# main_ftdi.net
KiCad netlist of a schematic drawn in Altium Designer
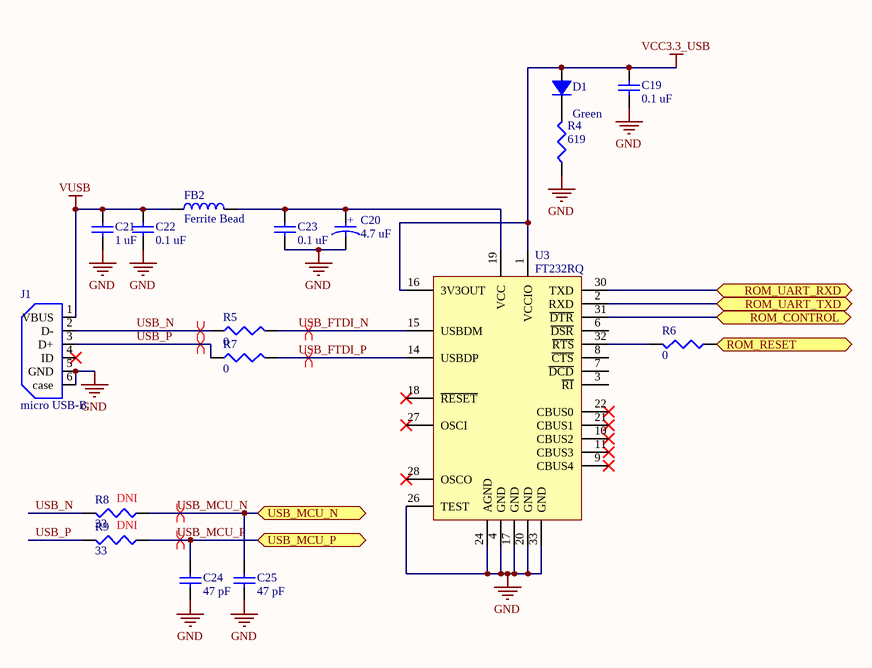
[diagram p0: main_ftdi.SchDoc]

(export (version "E")
  (design (tool "Eeschema 10.0.6"))
  (components
    (comp (ref "C19")
      (value "0.1 uF")
      (footprint "0402")
      (description "Ceramic capacitor, 0.1u, 0402 package")
      (fields (field (name "TOLERANCE") "10%") (field (name "Comment") "Ceramic capacitor"))
      (libsource (lib "rlc") (part "C_0.1u_0402_ceramic"))
    )
    (comp (ref "C20")
      (value "4.7 uF")
      (footprint "0603 - Polar Marking")
      (description "Tantalum capacitor, 4.7 uF, 0603 package")
      (fields (field (name "TOLERANCE") "20%") (field (name "Comment") "Tantalum capacitor"))
      (libsource (lib "rlc") (part "C_4.7u_0603_tantalum"))
    )
    (comp (ref "C21")
      (value "1 uF")
      (footprint "0402")
      (description "Ceramic capacitor, 1 uF, 0402 package")
      (fields (field (name "TOLERANCE") "10%") (field (name "Comment") "Ceramic capacitor"))
      (libsource (lib "rlc") (part "C_1u_0402_ceramic"))
    )
    (comp (ref "C22")
      (value "0.1 uF")
      (footprint "0402")
      (description "Ceramic capacitor, 0.1u, 0402 package")
      (fields (field (name "TOLERANCE") "10%") (field (name "Comment") "Ceramic capacitor"))
      (libsource (lib "rlc") (part "C_0.1u_0402_ceramic"))
    )
    (comp (ref "C23")
      (value "0.1 uF")
      (footprint "0402")
      (description "Ceramic capacitor, 0.1u, 0402 package")
      (fields (field (name "TOLERANCE") "10%") (field (name "Comment") "Ceramic capacitor"))
      (libsource (lib "rlc") (part "C_0.1u_0402_ceramic"))
    )
    (comp (ref "C24")
      (value "47 pF")
      (footprint "0402")
      (description "Ceramic capacitor, 47 pF, 0402 package")
      (fields (field (name "TOLERANCE") "5%") (field (name "Comment") "Ceramic capacitor"))
      (libsource (lib "rlc") (part "C_47p_0402_ceramic"))
    )
    (comp (ref "C25")
      (value "47 pF")
      (footprint "0402")
      (description "Ceramic capacitor, 47 pF, 0402 package")
      (fields (field (name "TOLERANCE") "5%") (field (name "Comment") "Ceramic capacitor"))
      (libsource (lib "rlc") (part "C_47p_0402_ceramic"))
    )
    (comp (ref "D1")
      (value "LED, Green")
      (footprint "0402 - DIODE")
      (description "LED, Green,  0402")
      (fields (field (name "COLOR") "Green"))
      (libsource (lib "rlc") (part "D_LED_GREEN_0402"))
    )
    (comp (ref "FB2")
      (value "Ferrite Bead")
      (footprint "0402")
      (description "Ferrite Bead, 150 mA, 0402 package")
      (libsource (lib "rlc") (part "FB_150mA_0402"))
    )
    (comp (ref "J1")
      (value "micro USB-B")
      (footprint "Micro USB-B")
      (description "CONN USB MICRO B RECPT SMT R/A")
      (libsource (lib "connectors") (part "Micro USB"))
    )
    (comp (ref "R4")
      (value "619")
      (footprint "0402")
      (description "Chip resistor, 619, 0402 package")
      (fields (field (name "TOLERANCE") "1%") (field (name "POWER") "1/16 W"))
      (libsource (lib "rlc") (part "R_619_0402"))
    )
    (comp (ref "R5")
      (value "0")
      (footprint "0402")
      (description "Chip resistor, 0, 0402 package")
      (fields (field (name "Comment") "Chip resistor"))
      (libsource (lib "rlc") (part "R_0_0402"))
    )
    (comp (ref "R6")
      (value "0")
      (footprint "0402")
      (description "Chip resistor, 0, 0402 package")
      (fields (field (name "Comment") "Chip resistor"))
      (libsource (lib "rlc") (part "R_0_0402"))
    )
    (comp (ref "R7")
      (value "0")
      (footprint "0402")
      (description "Chip resistor, 0, 0402 package")
      (fields (field (name "Comment") "Chip resistor"))
      (libsource (lib "rlc") (part "R_0_0402"))
    )
    (comp (ref "R8")
      (value "33")
      (footprint "0402")
      (description "Chip resistor, 33, 0402 package")
      (fields (field (name "TOLERANCE") "1%") (field (name "POWER") "1/16 W"))
      (libsource (lib "rlc") (part "R_33_0402"))
    )
    (comp (ref "R9")
      (value "33")
      (footprint "0402")
      (description "Chip resistor, 33, 0402 package")
      (fields (field (name "TOLERANCE") "1%") (field (name "POWER") "1/16 W"))
      (libsource (lib "rlc") (part "R_33_0402"))
    )
    (comp (ref "U3")
      (value "FT232RQ")
      (footprint "QFN-32")
      (description "FT232R USB UART")
      (libsource (lib "sdl") (part "FT232RQ"))
    )
  )
  (nets
    (net (code "1") (name "/ROM_CONTROL") (class "Default")
      (node (ref "U3") (pin "31") (pinfunction "~{DTR}_31") (pintype "passive"))
    )
    (net (code "2") (name "/ROM_RESET") (class "Default") (node (ref "R6") (pin "2") (pintype "passive")))
    (net (code "3") (name "/ROM_UART_RXD") (class "Default")
      (node (ref "U3") (pin "30") (pinfunction "TXD_30") (pintype "passive"))
    )
    (net (code "4") (name "/ROM_UART_TXD") (class "Default")
      (node (ref "U3") (pin "2") (pinfunction "RXD_2") (pintype "passive"))
    )
    (net (code "5") (name "/USB_FTDI_N") (class "Default")
      (node (ref "R5") (pin "1") (pintype "passive"))
      (node (ref "U3") (pin "15") (pinfunction "USBDM_15") (pintype "passive"))
    )
    (net (code "6") (name "/USB_FTDI_P") (class "Default")
      (node (ref "R7") (pin "1") (pintype "passive"))
      (node (ref "U3") (pin "14") (pinfunction "USBDP_14") (pintype "passive"))
    )
    (net (code "7") (name "/USB_MCU_N") (class "Default")
      (node (ref "C25") (pin "1") (pintype "passive"))
      (node (ref "R8") (pin "2") (pintype "passive"))
    )
    (net (code "8") (name "/USB_MCU_P") (class "Default")
      (node (ref "C24") (pin "1") (pintype "passive"))
      (node (ref "R9") (pin "2") (pintype "passive"))
    )
    (net (code "9") (name "/USB_N") (class "Default")
      (node (ref "J1") (pin "2") (pinfunction "D-_2") (pintype "power_in"))
      (node (ref "R5") (pin "2") (pintype "passive"))
      (node (ref "R8") (pin "1") (pintype "passive"))
    )
    (net (code "10") (name "/USB_P") (class "Default")
      (node (ref "J1") (pin "3") (pinfunction "D+_3") (pintype "power_in"))
      (node (ref "R7") (pin "2") (pintype "passive"))
      (node (ref "R9") (pin "1") (pintype "passive"))
    )
    (net (code "11") (name "GND") (class "Default")
      (node (ref "C19") (pin "2") (pintype "passive"))
      (node (ref "C20") (pin "2") (pintype "passive"))
      (node (ref "C21") (pin "2") (pintype "passive"))
      (node (ref "C22") (pin "2") (pintype "passive"))
      (node (ref "C23") (pin "2") (pintype "passive"))
      (node (ref "C24") (pin "2") (pintype "passive"))
      (node (ref "C25") (pin "2") (pintype "passive"))
      (node (ref "J1") (pin "5") (pinfunction "GND_5") (pintype "power_in"))
      (node (ref "J1") (pin "6") (pinfunction "case_6") (pintype "power_in"))
      (node (ref "R4") (pin "2") (pintype "passive"))
      (node (ref "U3") (pin "17") (pinfunction "GND_17") (pintype "passive"))
      (node (ref "U3") (pin "20") (pinfunction "GND_20") (pintype "passive"))
      (node (ref "U3") (pin "24") (pinfunction "AGND_24") (pintype "passive"))
      (node (ref "U3") (pin "26") (pinfunction "TEST_26") (pintype "passive"))
      (node (ref "U3") (pin "33") (pinfunction "GND_33") (pintype "passive"))
      (node (ref "U3") (pin "4") (pinfunction "GND_4") (pintype "passive"))
    )
    (net (code "12") (name "Net-(D1-Pad2)") (class "Default")
      (node (ref "D1") (pin "2") (pintype "passive"))
      (node (ref "R4") (pin "1") (pintype "passive"))
    )
    (net (code "13") (name "Net-(U3-VCC)") (class "Default")
      (node (ref "C20") (pin "1") (pintype "passive"))
      (node (ref "C23") (pin "1") (pintype "passive"))
      (node (ref "FB2") (pin "1") (pintype "passive"))
      (node (ref "U3") (pin "19") (pinfunction "VCC_19") (pintype "passive"))
    )
    (net (code "14") (name "Net-(U3-~{RTS})") (class "Default")
      (node (ref "R6") (pin "1") (pintype "passive"))
      (node (ref "U3") (pin "32") (pinfunction "~{RTS}_32") (pintype "passive"))
    )
    (net (code "15") (name "VCC3.3_USB") (class "Default")
      (node (ref "C19") (pin "1") (pintype "passive"))
      (node (ref "D1") (pin "1") (pintype "passive"))
      (node (ref "U3") (pin "1") (pinfunction "VCCIO_1") (pintype "passive"))
      (node (ref "U3") (pin "16") (pinfunction "3V3OUT_16") (pintype "passive"))
    )
    (net (code "16") (name "VUSB") (class "Default")
      (node (ref "C21") (pin "1") (pintype "passive"))
      (node (ref "C22") (pin "1") (pintype "passive"))
      (node (ref "FB2") (pin "2") (pintype "passive"))
      (node (ref "J1") (pin "1") (pinfunction "VBUS_1") (pintype "power_in"))
    )
    (net (code "17") (name "unconnected-(J1-ID-Pad4)") (class "Default")
      (node (ref "J1") (pin "4") (pinfunction "ID_4") (pintype "power_in+no_connect"))
    )
    (net (code "18") (name "unconnected-(U3-CBUS0-Pad22)") (class "Default")
      (node (ref "U3") (pin "22") (pinfunction "CBUS0_22") (pintype "passive+no_connect"))
    )
    (net (code "19") (name "unconnected-(U3-CBUS1-Pad21)") (class "Default")
      (node (ref "U3") (pin "21") (pinfunction "CBUS1_21") (pintype "passive+no_connect"))
    )
    (net (code "20") (name "unconnected-(U3-CBUS2-Pad10)") (class "Default")
      (node (ref "U3") (pin "10") (pinfunction "CBUS2_10") (pintype "passive+no_connect"))
    )
    (net (code "21") (name "unconnected-(U3-CBUS3-Pad11)") (class "Default")
      (node (ref "U3") (pin "11") (pinfunction "CBUS3_11") (pintype "passive+no_connect"))
    )
    (net (code "22") (name "unconnected-(U3-CBUS4-Pad9)") (class "Default")
      (node (ref "U3") (pin "9") (pinfunction "CBUS4_9") (pintype "passive+no_connect"))
    )
    (net (code "23") (name "unconnected-(U3-OSCI-Pad27)") (class "Default")
      (node (ref "U3") (pin "27") (pinfunction "OSCI_27") (pintype "passive+no_connect"))
    )
    (net (code "24") (name "unconnected-(U3-OSCO-Pad28)") (class "Default")
      (node (ref "U3") (pin "28") (pinfunction "OSCO_28") (pintype "passive+no_connect"))
    )
    (net (code "25") (name "unconnected-(U3-~{CTS}-Pad8)") (class "Default")
      (node (ref "U3") (pin "8") (pinfunction "~{CTS}_8") (pintype "passive"))
    )
    (net (code "26") (name "unconnected-(U3-~{DCD}-Pad7)") (class "Default")
      (node (ref "U3") (pin "7") (pinfunction "~{DCD}_7") (pintype "passive"))
    )
    (net (code "27") (name "unconnected-(U3-~{DSR}-Pad6)") (class "Default")
      (node (ref "U3") (pin "6") (pinfunction "~{DSR}_6") (pintype "passive"))
    )
    (net (code "28") (name "unconnected-(U3-~{RESET}-Pad18)") (class "Default")
      (node (ref "U3") (pin "18") (pinfunction "~{RESET}_18") (pintype "passive+no_connect"))
    )
    (net (code "29") (name "unconnected-(U3-~{RI}-Pad3)") (class "Default")
      (node (ref "U3") (pin "3") (pinfunction "~{RI}_3") (pintype "passive"))
    )
  )
)
